# RS485.net
KiCad netlist of a schematic drawn in Altium Designer
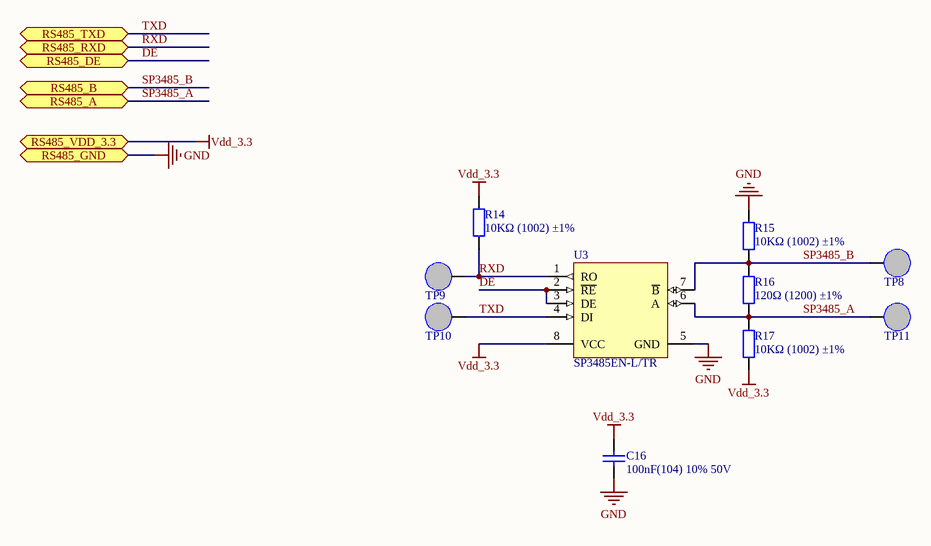
[diagram p0: RS485.SchDoc]

(export (version "E")
  (design (tool "Eeschema 10.0.6"))
  (components
    (comp (ref "C16")
      (value "100nF(104) 10% 50V")
      (footprint "0805_C")
      (description "贴片电容")
      (libsource (lib "Miscellaneous Devices LC") (part "0805 100nF(104) 10% 50V"))
    )
    (comp (ref "R14")
      (value "10KΩ (1002) ±1%")
      (footprint "0805_R")
      (description "贴片电阻")
      (libsource (lib "Miscellaneous Devices LC") (part "0805 10KΩ (1002) 1%"))
    )
    (comp (ref "R15")
      (value "10KΩ (1002) ±1%")
      (footprint "0805_R")
      (description "贴片电阻")
      (libsource (lib "Miscellaneous Devices LC") (part "0805 10KΩ (1002) 1%"))
    )
    (comp (ref "R16")
      (value "120Ω (1200) ±1%")
      (footprint "0805_R")
      (description "贴片电阻")
      (libsource (lib "Miscellaneous Devices LC") (part "0805 120Ω (1200) 1%"))
    )
    (comp (ref "R17")
      (value "10KΩ (1002) ±1%")
      (footprint "0805_R")
      (description "贴片电阻")
      (libsource (lib "Miscellaneous Devices LC") (part "0805 10KΩ (1002) 1%"))
    )
    (comp (ref "TP8") (value "TP") (footprint "TP") (libsource (lib "mylib") (part "TP")))
    (comp (ref "TP9") (value "TP") (footprint "TP") (libsource (lib "mylib") (part "TP")))
    (comp (ref "TP10") (value "TP") (footprint "TP") (libsource (lib "mylib") (part "TP")))
    (comp (ref "TP11") (value "TP") (footprint "TP") (libsource (lib "mylib") (part "TP")))
    (comp (ref "U3")
      (value "SP3485EN-L/TR")
      (footprint "SOIC-8_150mil")
      (description "RS-485/RS-422")
      (libsource (lib "Miscellaneous Devices LC") (part "SP3485EN-L/TR_[C8963]"))
    )
  )
  (nets
    (net (code "1") (name "/DE") (class "Default")
      (node (ref "U3") (pin "2") (pinfunction "~{RE}_2") (pintype "input"))
      (node (ref "U3") (pin "3") (pinfunction "DE_3") (pintype "input"))
    )
    (net (code "2") (name "/RXD") (class "Default")
      (node (ref "R14") (pin "1") (pinfunction "1_1") (pintype "passive"))
      (node (ref "TP9") (pin "1") (pinfunction "1_1") (pintype "passive"))
      (node (ref "U3") (pin "1") (pinfunction "RO_1") (pintype "output"))
    )
    (net (code "3") (name "/SP3485_A") (class "Default")
      (node (ref "R16") (pin "1") (pinfunction "1_1") (pintype "passive"))
      (node (ref "R17") (pin "2") (pinfunction "2_2") (pintype "passive"))
      (node (ref "TP11") (pin "1") (pinfunction "1_1") (pintype "passive"))
      (node (ref "U3") (pin "6") (pinfunction "A_6") (pintype "bidirectional"))
    )
    (net (code "4") (name "/SP3485_B") (class "Default")
      (node (ref "R15") (pin "1") (pinfunction "1_1") (pintype "passive"))
      (node (ref "R16") (pin "2") (pinfunction "2_2") (pintype "passive"))
      (node (ref "TP8") (pin "1") (pinfunction "1_1") (pintype "passive"))
      (node (ref "U3") (pin "7") (pinfunction "~{B}_7") (pintype "bidirectional"))
    )
    (net (code "5") (name "/TXD") (class "Default")
      (node (ref "TP10") (pin "1") (pinfunction "1_1") (pintype "passive"))
      (node (ref "U3") (pin "4") (pinfunction "DI_4") (pintype "input"))
    )
    (net (code "6") (name "GND") (class "Default")
      (node (ref "C16") (pin "2") (pinfunction "2_2") (pintype "passive"))
      (node (ref "R15") (pin "2") (pinfunction "2_2") (pintype "passive"))
      (node (ref "U3") (pin "5") (pinfunction "GND_5") (pintype "power_in"))
    )
    (net (code "7") (name "Vdd_3.3") (class "Default")
      (node (ref "C16") (pin "1") (pinfunction "1_1") (pintype "passive"))
      (node (ref "R14") (pin "2") (pinfunction "2_2") (pintype "passive"))
      (node (ref "R17") (pin "1") (pinfunction "1_1") (pintype "passive"))
      (node (ref "U3") (pin "8") (pinfunction "VCC_8") (pintype "power_in"))
    )
  )
)
